# TOP.net
KiCad netlist of a schematic drawn in Altium Designer
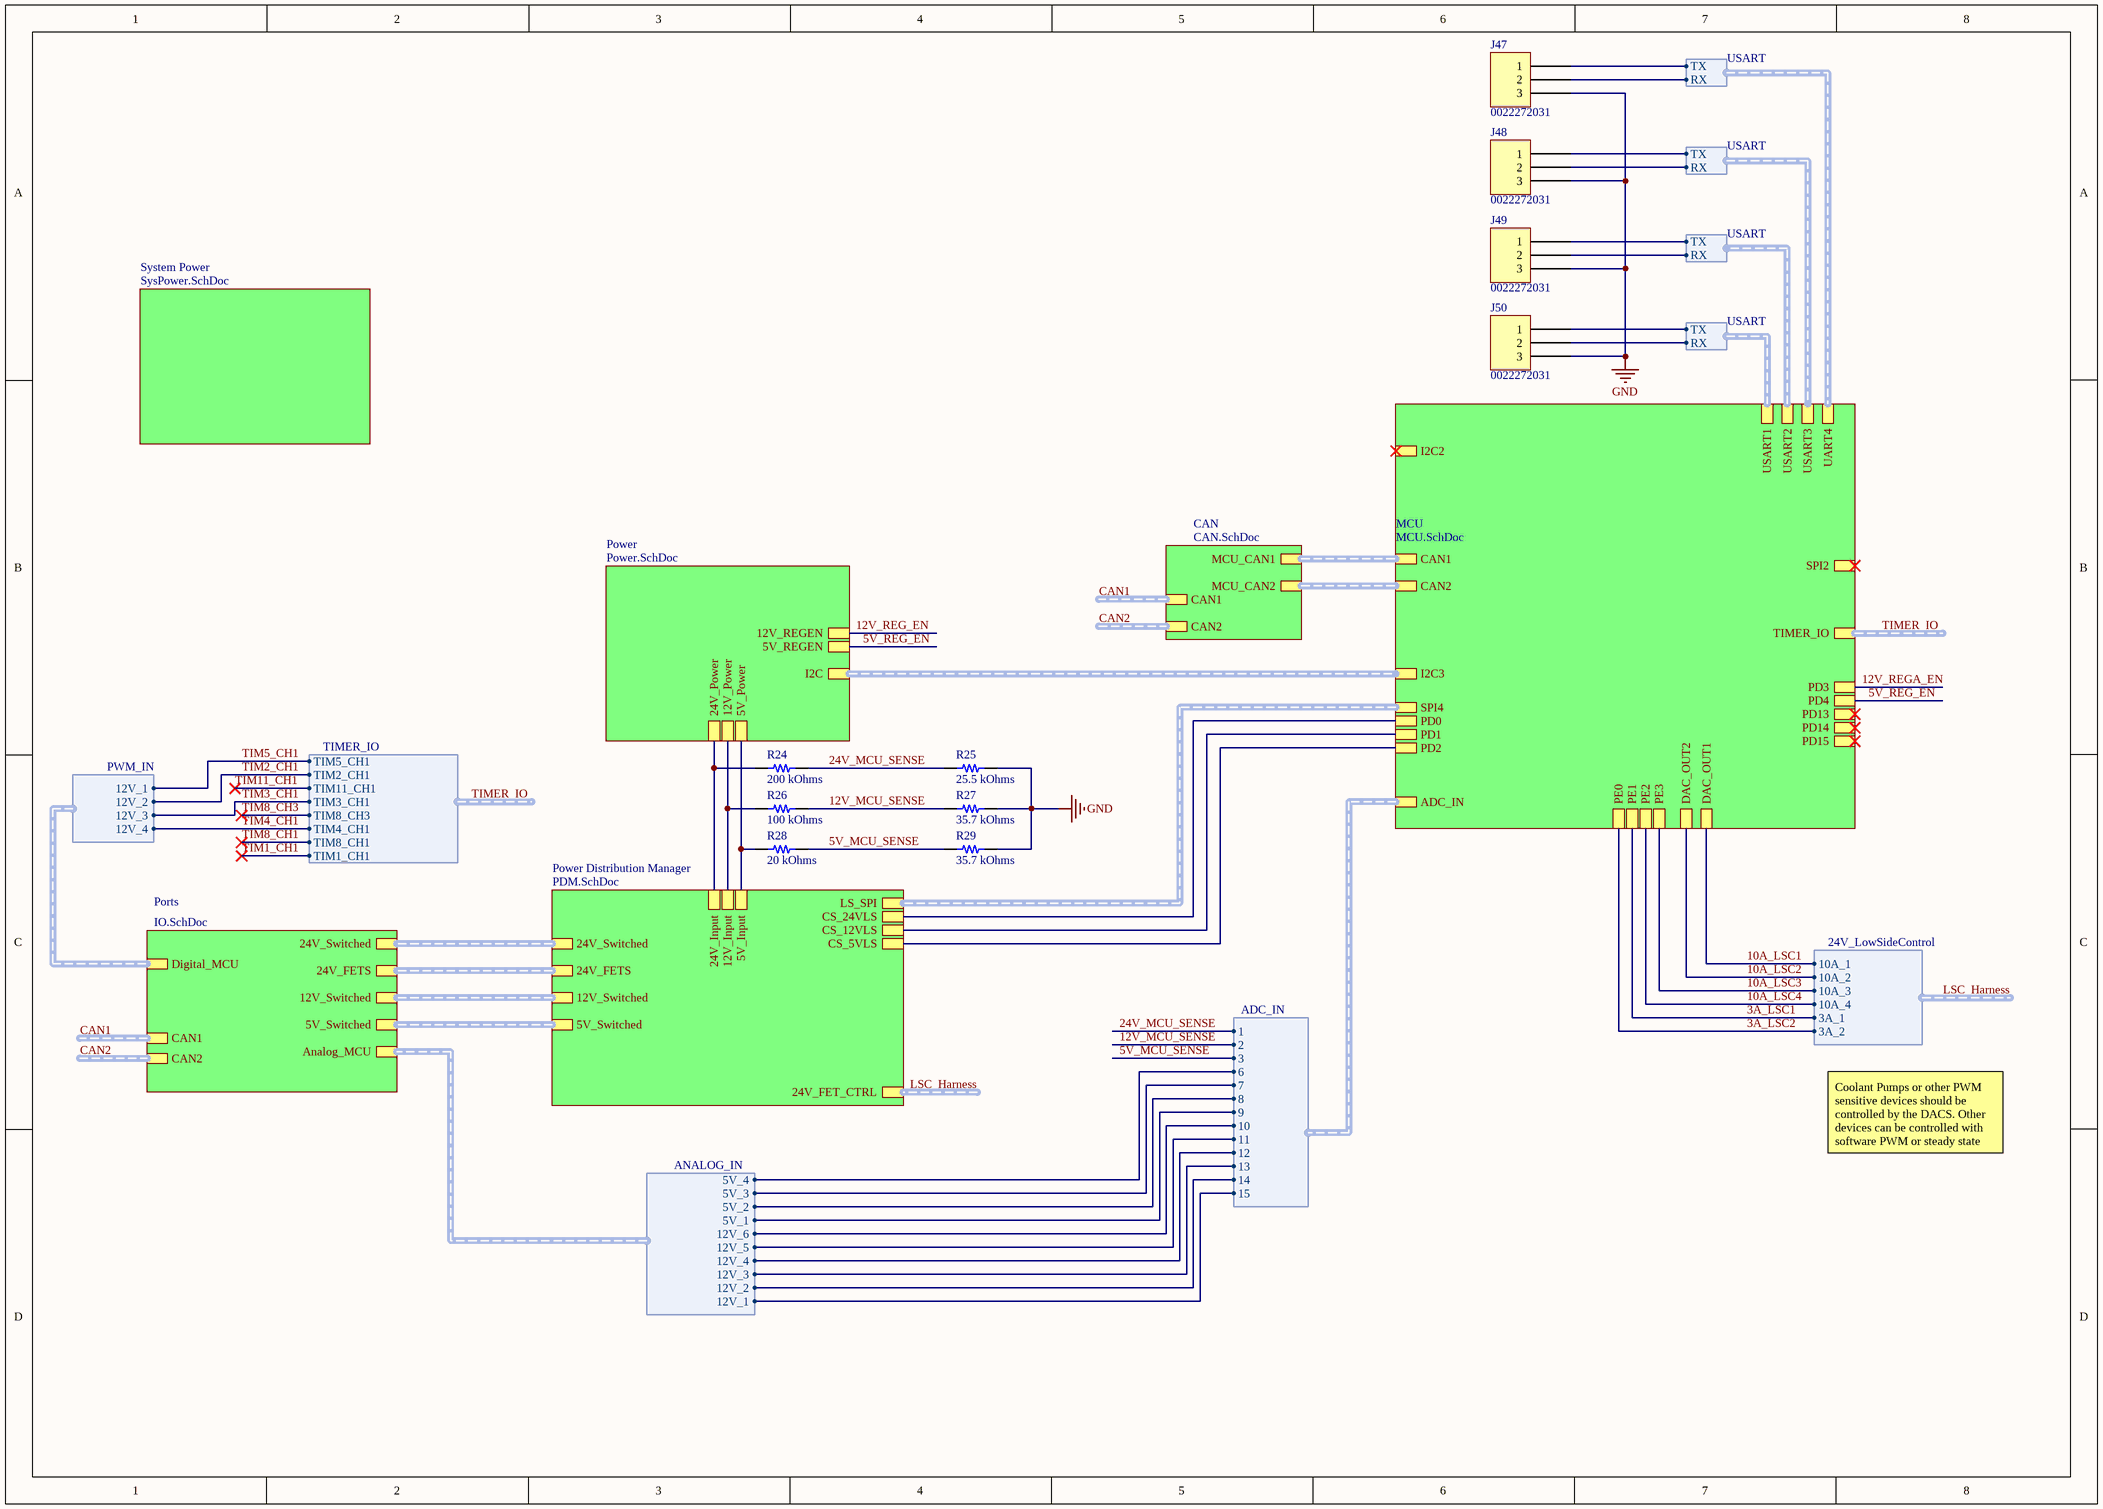
[diagram p0: TOP.SchDoc]

(export (version "E")
  (design (tool "Eeschema 10.0.6"))
  (components
    (comp (ref "J47")
      (value "0022272031")
      (footprint "MOLEX KK 0022272031")
      (description "CONN HEADER VERT 3POS 2.54MM")
      (libsource (lib "altium_library") (part "3 Pin"))
    )
    (comp (ref "J48")
      (value "0022272031")
      (footprint "MOLEX KK 0022272031")
      (description "CONN HEADER VERT 3POS 2.54MM")
      (libsource (lib "altium_library") (part "3 Pin"))
    )
    (comp (ref "J49")
      (value "0022272031")
      (footprint "MOLEX KK 0022272031")
      (description "CONN HEADER VERT 3POS 2.54MM")
      (libsource (lib "altium_library") (part "3 Pin"))
    )
    (comp (ref "J50")
      (value "0022272031")
      (footprint "MOLEX KK 0022272031")
      (description "CONN HEADER VERT 3POS 2.54MM")
      (libsource (lib "altium_library") (part "3 Pin"))
    )
    (comp (ref "R24")
      (value "200 kOhms")
      (footprint "RES 0603_1608")
      (description "RES SMD 200K OHM 1% 1/10W 0603")
      (fields (field (name "PART NUMBER") "AC0603FR-07200KL") (field (name "MANUFACTURER") "Yageo"))
      (libsource (lib "altium_library") (part "Resistor"))
    )
    (comp (ref "R25")
      (value "25.5 kOhms")
      (footprint "RES 0603_1608")
      (description "RES SMD 25.5KOHM 0.1% 1/16W 0603")
      (fields
        (field (name "PART NUMBER") "CPF0603B25K5E1")
        (field (name "MANUFACTURER") "TE Connectivity Passive Product")
      )
      (libsource (lib "altium_library") (part "Resistor"))
    )
    (comp (ref "R26")
      (value "100 kOhms")
      (footprint "RES 0603_1608")
      (description "RES SMD 100K OHM 1% 1/10W 0603")
      (fields (field (name "PART NUMBER") "AA0603FR-07100KL") (field (name "MANUFACTURER") "Yageo"))
      (libsource (lib "altium_library") (part "Resistor"))
    )
    (comp (ref "R27")
      (value "35.7 kOhms")
      (footprint "RES 0603_1608")
      (description "RES SMD 35.7KOHM 0.1% 1/10W 0603")
      (fields (field (name "PART NUMBER") "RT0603BRD0735K7L") (field (name "MANUFACTURER") "Yageo"))
      (libsource (lib "altium_library") (part "Resistor"))
    )
    (comp (ref "R28")
      (value "20 kOhms")
      (footprint "RES 0603_1608")
      (description "RES SMD 20K OHM 1% 1/10W 0603")
      (fields (field (name "PART NUMBER") "AC0603FR-0720KL") (field (name "MANUFACTURER") "Yageo"))
      (libsource (lib "altium_library") (part "Resistor"))
    )
    (comp (ref "R29")
      (value "35.7 kOhms")
      (footprint "RES 0603_1608")
      (description "RES SMD 35.7KOHM 0.1% 1/10W 0603")
      (fields (field (name "PART NUMBER") "RT0603BRD0735K7L") (field (name "MANUFACTURER") "Yageo"))
      (libsource (lib "altium_library") (part "Resistor"))
    )
  )
  (nets
    (net (code "13") (name "/5V_Input") (class "Default")
      (node (ref "R28") (pin "1") (pinfunction "1_1") (pintype "passive"))
    )
    (net (code "14") (name "/5V_MCU_SENSE") (class "Default")
      (node (ref "R28") (pin "2") (pinfunction "2_2") (pintype "passive"))
      (node (ref "R29") (pin "1") (pinfunction "1_1") (pintype "passive"))
    )
    (net (code "21") (name "/12V_Input") (class "Default")
      (node (ref "R26") (pin "1") (pinfunction "1_1") (pintype "passive"))
    )
    (net (code "22") (name "/12V_MCU_SENSE") (class "Default")
      (node (ref "R26") (pin "2") (pinfunction "2_2") (pintype "passive"))
      (node (ref "R27") (pin "1") (pinfunction "1_1") (pintype "passive"))
    )
    (net (code "27") (name "/24V_Input") (class "Default")
      (node (ref "R24") (pin "1") (pinfunction "1_1") (pintype "passive"))
    )
    (net (code "28") (name "/24V_MCU_SENSE") (class "Default")
      (node (ref "R24") (pin "2") (pinfunction "2_2") (pintype "passive"))
      (node (ref "R25") (pin "1") (pinfunction "1_1") (pintype "passive"))
    )
    (net (code "60") (name "GND") (class "Default")
      (node (ref "J47") (pin "3") (pinfunction "3_3") (pintype "passive"))
      (node (ref "J48") (pin "3") (pinfunction "3_3") (pintype "passive"))
      (node (ref "J49") (pin "3") (pinfunction "3_3") (pintype "passive"))
      (node (ref "J50") (pin "3") (pinfunction "3_3") (pintype "passive"))
      (node (ref "R25") (pin "2") (pinfunction "2_2") (pintype "passive"))
      (node (ref "R27") (pin "2") (pinfunction "2_2") (pintype "passive"))
      (node (ref "R29") (pin "2") (pinfunction "2_2") (pintype "passive"))
    )
    (net (code "61") (name "unconnected-(J47-Pad1)") (class "Default")
      (node (ref "J47") (pin "1") (pinfunction "1_1") (pintype "passive"))
    )
    (net (code "62") (name "unconnected-(J47-Pad2)") (class "Default")
      (node (ref "J47") (pin "2") (pinfunction "2_2") (pintype "passive"))
    )
    (net (code "63") (name "unconnected-(J48-Pad1)") (class "Default")
      (node (ref "J48") (pin "1") (pinfunction "1_1") (pintype "passive"))
    )
    (net (code "64") (name "unconnected-(J48-Pad2)") (class "Default")
      (node (ref "J48") (pin "2") (pinfunction "2_2") (pintype "passive"))
    )
    (net (code "65") (name "unconnected-(J49-Pad1)") (class "Default")
      (node (ref "J49") (pin "1") (pinfunction "1_1") (pintype "passive"))
    )
    (net (code "66") (name "unconnected-(J49-Pad2)") (class "Default")
      (node (ref "J49") (pin "2") (pinfunction "2_2") (pintype "passive"))
    )
    (net (code "67") (name "unconnected-(J50-Pad1)") (class "Default")
      (node (ref "J50") (pin "1") (pinfunction "1_1") (pintype "passive"))
    )
    (net (code "68") (name "unconnected-(J50-Pad2)") (class "Default")
      (node (ref "J50") (pin "2") (pinfunction "2_2") (pintype "passive"))
    )
  )
)
